# TH02.net
KiCad netlist of a schematic drawn in Altium Designer
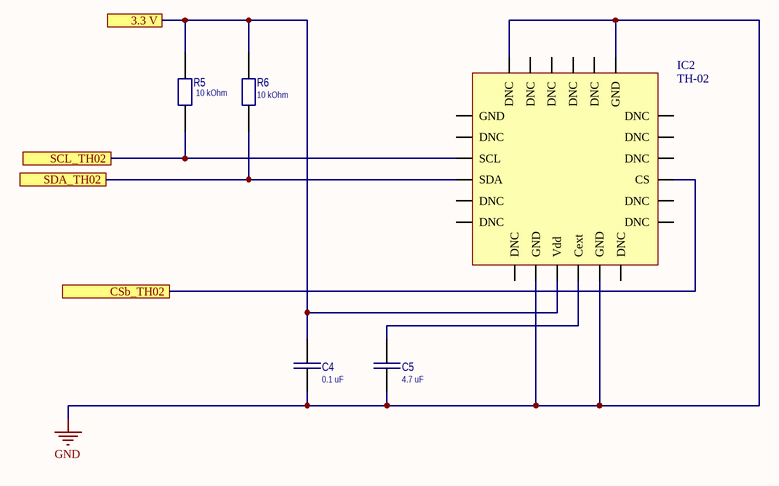
[diagram p0: TH02.SchDoc]

(export (version "E")
  (design (tool "Eeschema 10.0.6"))
  (components
    (comp (ref "C4")
      (value "0.1 uF")
      (footprint "C_0805")
      (description "Capacitor")
      (libsource (lib "capacitors") (part "C0805"))
    )
    (comp (ref "C5")
      (value "4.7 uF")
      (footprint "C_0805")
      (description "Capacitor")
      (libsource (lib "capacitors") (part "C0805"))
    )
    (comp (ref "IC2")
      (value "TH-02")
      (footprint "TH-02")
      (description "Temperature and humidity sensor")
      (libsource (lib "Sensors") (part "TH_02"))
    )
    (comp (ref "R5")
      (value "10 kOhm")
      (footprint "R_0805")
      (description "Resistor")
      (libsource (lib "resistors") (part "R0805"))
    )
    (comp (ref "R6")
      (value "10 kOhm")
      (footprint "R_0805")
      (description "Resistor")
      (libsource (lib "resistors") (part "R0805"))
    )
  )
  (nets
    (net (code "1") (name "/3.3 V") (class "Default")
      (node (ref "C4") (pin "2") (pinfunction "2_2") (pintype "passive"))
      (node (ref "IC2") (pin "9") (pinfunction "Vdd_9") (pintype "passive"))
      (node (ref "R5") (pin "2") (pinfunction "2_2") (pintype "passive"))
      (node (ref "R6") (pin "2") (pinfunction "2_2") (pintype "passive"))
    )
    (net (code "2") (name "/CSb_TH02") (class "Default")
      (node (ref "IC2") (pin "15") (pinfunction "CS_15") (pintype "bidirectional"))
    )
    (net (code "3") (name "/SCL_TH02") (class "Default")
      (node (ref "IC2") (pin "3") (pinfunction "SCL_3") (pintype "passive"))
      (node (ref "R5") (pin "1") (pinfunction "1_1") (pintype "passive"))
    )
    (net (code "4") (name "/SDA_TH02") (class "Default")
      (node (ref "IC2") (pin "4") (pinfunction "SDA_4") (pintype "passive"))
      (node (ref "R6") (pin "1") (pinfunction "1_1") (pintype "passive"))
    )
    (net (code "5") (name "GND") (class "Default")
      (node (ref "C4") (pin "1") (pinfunction "1_1") (pintype "passive"))
      (node (ref "C5") (pin "1") (pinfunction "1_1") (pintype "passive"))
      (node (ref "IC2") (pin "11") (pinfunction "GND_11") (pintype "passive"))
      (node (ref "IC2") (pin "19") (pinfunction "GND_19") (pintype "passive"))
      (node (ref "IC2") (pin "24") (pinfunction "DNC_24") (pintype "passive"))
      (node (ref "IC2") (pin "8") (pinfunction "GND_8") (pintype "passive"))
    )
    (net (code "6") (name "Net-(IC2-Cext)") (class "Default")
      (node (ref "C5") (pin "2") (pinfunction "2_2") (pintype "passive"))
      (node (ref "IC2") (pin "10") (pinfunction "Cext_10") (pintype "passive"))
    )
    (net (code "7") (name "unconnected-(IC2-DNC-Pad2)") (class "Default")
      (node (ref "IC2") (pin "2") (pinfunction "DNC_2") (pintype "passive"))
    )
    (net (code "8") (name "unconnected-(IC2-DNC-Pad5)") (class "Default")
      (node (ref "IC2") (pin "5") (pinfunction "DNC_5") (pintype "passive"))
    )
    (net (code "9") (name "unconnected-(IC2-DNC-Pad6)") (class "Default")
      (node (ref "IC2") (pin "6") (pinfunction "DNC_6") (pintype "passive"))
    )
    (net (code "10") (name "unconnected-(IC2-DNC-Pad7)") (class "Default")
      (node (ref "IC2") (pin "7") (pinfunction "DNC_7") (pintype "passive"))
    )
    (net (code "11") (name "unconnected-(IC2-DNC-Pad12)") (class "Default")
      (node (ref "IC2") (pin "12") (pinfunction "DNC_12") (pintype "passive"))
    )
    (net (code "12") (name "unconnected-(IC2-DNC-Pad13)") (class "Default")
      (node (ref "IC2") (pin "13") (pinfunction "DNC_13") (pintype "passive"))
    )
    (net (code "13") (name "unconnected-(IC2-DNC-Pad14)") (class "Default")
      (node (ref "IC2") (pin "14") (pinfunction "DNC_14") (pintype "passive"))
    )
    (net (code "14") (name "unconnected-(IC2-DNC-Pad16)") (class "Default")
      (node (ref "IC2") (pin "16") (pinfunction "DNC_16") (pintype "passive"))
    )
    (net (code "15") (name "unconnected-(IC2-DNC-Pad17)") (class "Default")
      (node (ref "IC2") (pin "17") (pinfunction "DNC_17") (pintype "passive"))
    )
    (net (code "16") (name "unconnected-(IC2-DNC-Pad18)") (class "Default")
      (node (ref "IC2") (pin "18") (pinfunction "DNC_18") (pintype "passive"))
    )
    (net (code "17") (name "unconnected-(IC2-DNC-Pad20)") (class "Default")
      (node (ref "IC2") (pin "20") (pinfunction "DNC_20") (pintype "passive"))
    )
    (net (code "18") (name "unconnected-(IC2-DNC-Pad21)") (class "Default")
      (node (ref "IC2") (pin "21") (pinfunction "DNC_21") (pintype "passive"))
    )
    (net (code "19") (name "unconnected-(IC2-DNC-Pad22)") (class "Default")
      (node (ref "IC2") (pin "22") (pinfunction "DNC_22") (pintype "passive"))
    )
    (net (code "20") (name "unconnected-(IC2-DNC-Pad23)") (class "Default")
      (node (ref "IC2") (pin "23") (pinfunction "DNC_23") (pintype "passive"))
    )
    (net (code "21") (name "unconnected-(IC2-GND-Pad1)") (class "Default")
      (node (ref "IC2") (pin "1") (pinfunction "GND_1") (pintype "passive"))
    )
  )
)
